# datalogger.net
KiCad netlist of a schematic drawn in EAGLE
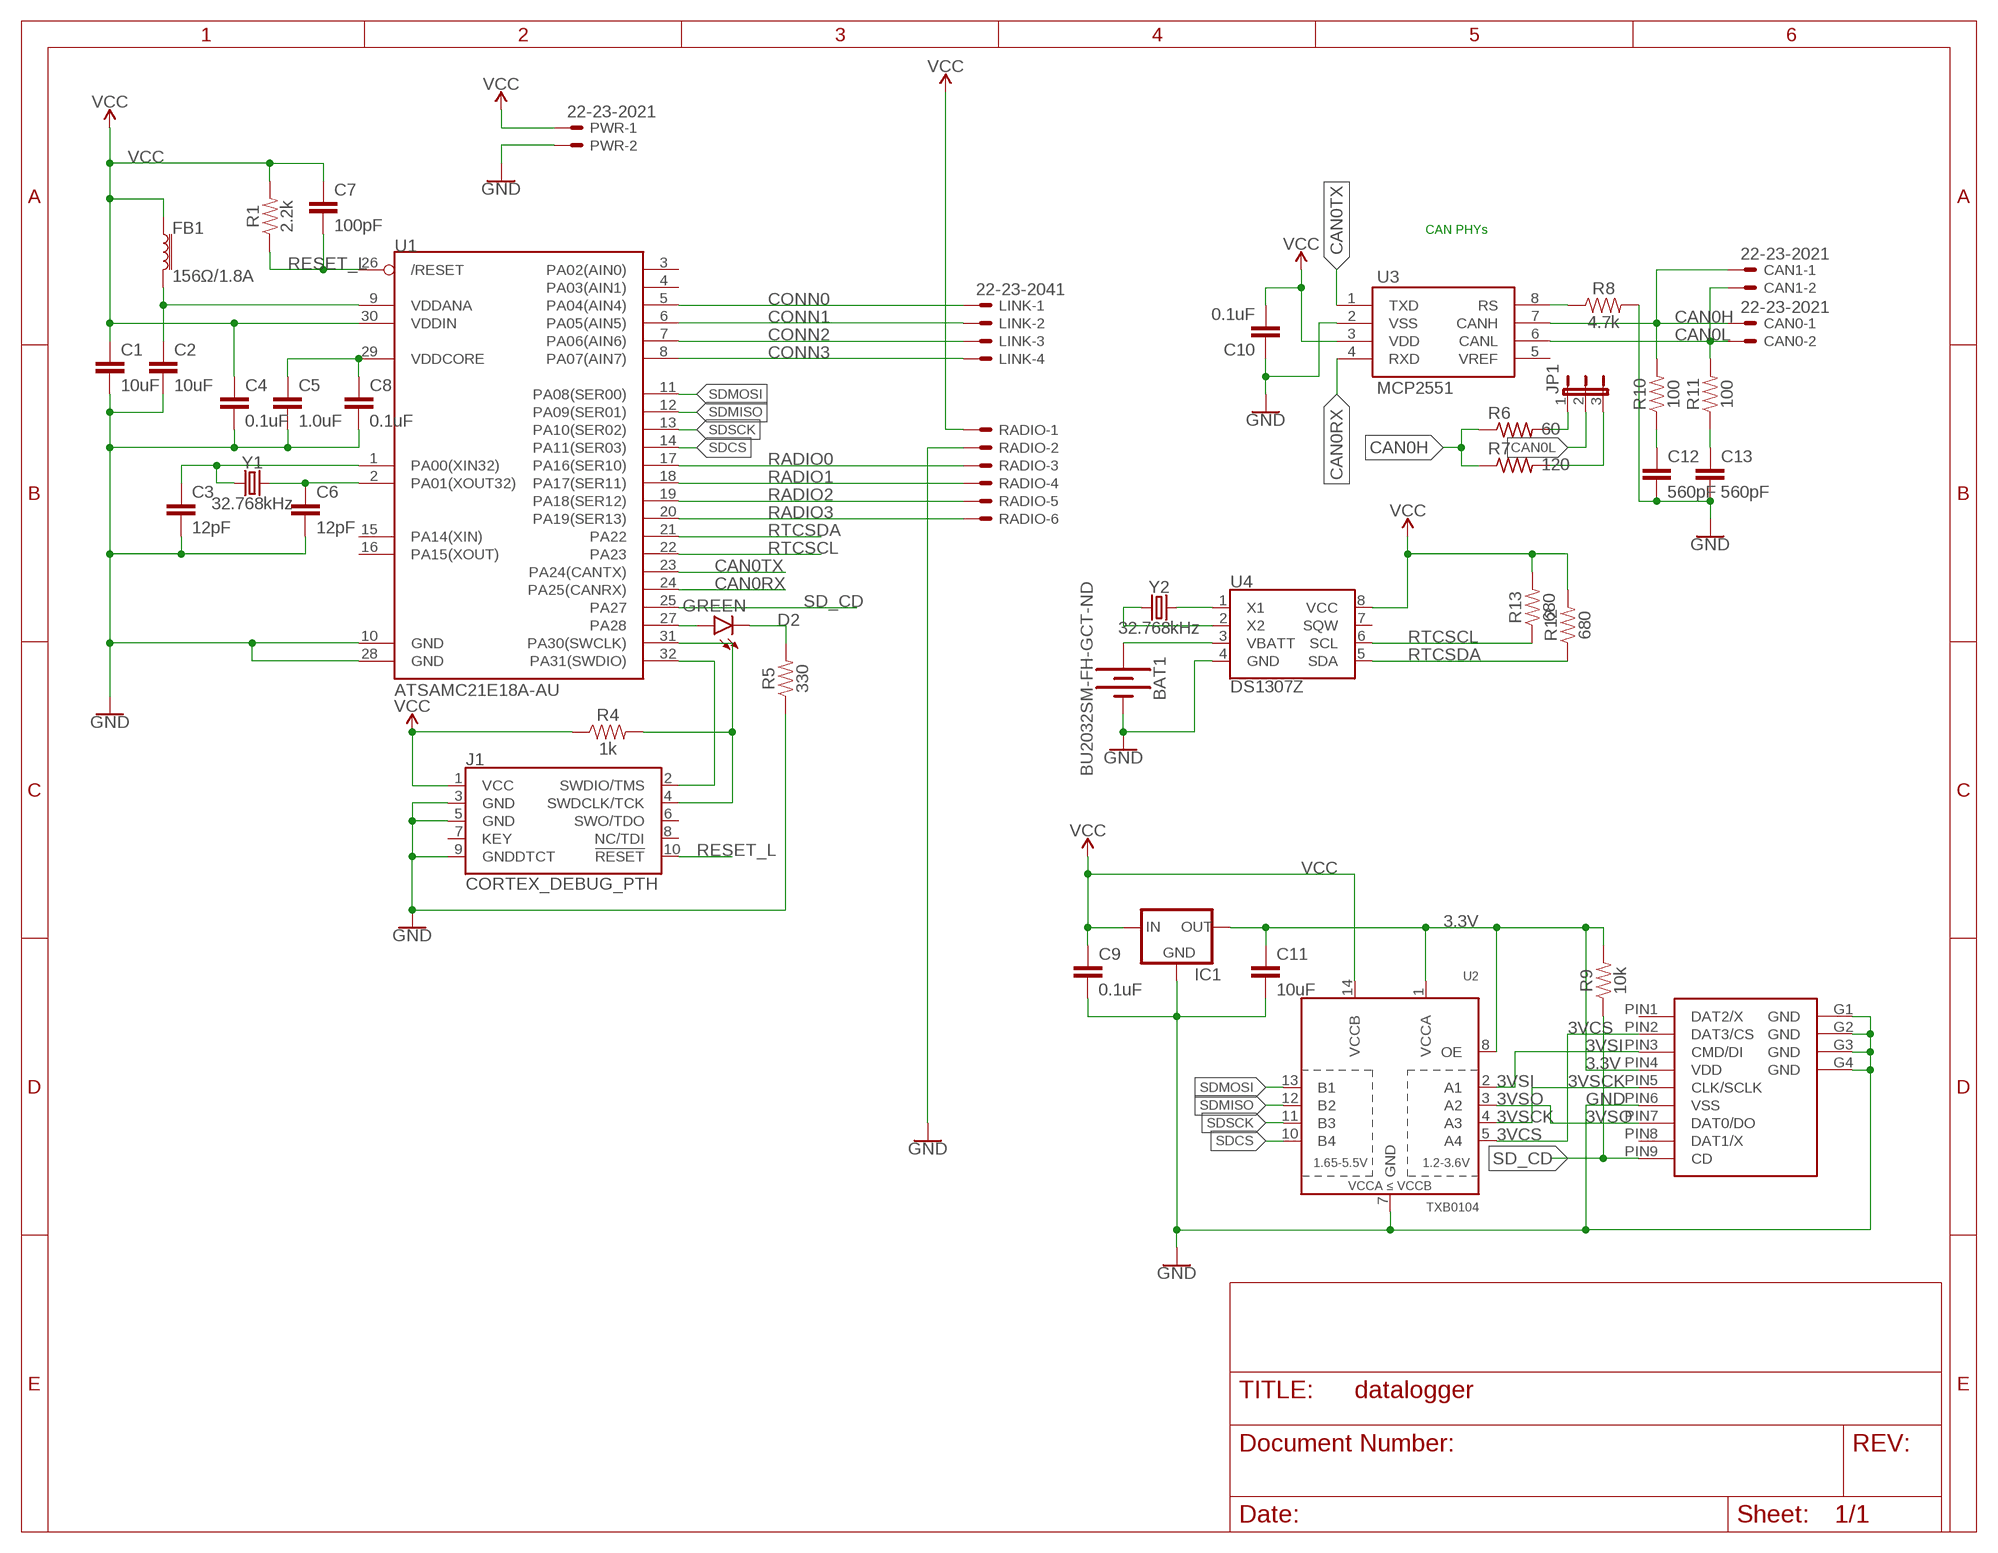
[diagram p0: schematic, sheet 1]

(export (version "E")
  (design (tool "Eeschema 10.0.6"))
  (components
    (comp (ref "BAT1")
      (value "BU2032SM-FH-GCT-ND")
      (footprint "eagle-import:BAT_BU2032SM-BT-GTR")
      (libsource (lib "eagle-import") (part "BU2032SM-FH-GCT-ND"))
    )
    (comp (ref "C1")
      (value "10uF")
      (footprint "eagle-import:0603")
      (libsource (lib "eagle-import") (part "10UF-0603-6.3V-20%"))
    )
    (comp (ref "C2")
      (value "10uF")
      (footprint "eagle-import:0603")
      (libsource (lib "eagle-import") (part "10UF-0603-6.3V-20%"))
    )
    (comp (ref "C3")
      (value "12pF")
      (footprint "eagle-import:0603")
      (libsource (lib "eagle-import") (part "12PF-0603-50V-5%"))
    )
    (comp (ref "C4")
      (value "0.1uF")
      (footprint "eagle-import:0603")
      (libsource (lib "eagle-import") (part "0.1UF-0603-25V-(+80/-20%)"))
    )
    (comp (ref "C5")
      (value "1.0uF")
      (footprint "eagle-import:0603")
      (libsource (lib "eagle-import") (part "1.0UF-0603-16V-10%"))
    )
    (comp (ref "C6")
      (value "12pF")
      (footprint "eagle-import:0603")
      (libsource (lib "eagle-import") (part "12PF-0603-50V-5%"))
    )
    (comp (ref "C7")
      (value "100pF")
      (footprint "eagle-import:0603")
      (libsource (lib "eagle-import") (part "100PF-0603-50V-5%"))
    )
    (comp (ref "C8")
      (value "0.1uF")
      (footprint "eagle-import:0603")
      (libsource (lib "eagle-import") (part "0.1UF-0603-25V-(+80/-20%)"))
    )
    (comp (ref "C9")
      (value "0.1uF")
      (footprint "eagle-import:0603")
      (libsource (lib "eagle-import") (part "0.1UF-0603-25V-(+80/-20%)"))
    )
    (comp (ref "C10")
      (value "0.1uF")
      (footprint "eagle-import:0603")
      (libsource (lib "eagle-import") (part "0.1UF-0603-25V-(+80/-20%)"))
    )
    (comp (ref "C11")
      (value "10uF")
      (footprint "eagle-import:0603")
      (libsource (lib "eagle-import") (part "10UF-0603-6.3V-20%"))
    )
    (comp (ref "C12")
      (value "560pF")
      (footprint "eagle-import:0603")
      (libsource (lib "eagle-import") (part "560PF-0603-50V-5%"))
    )
    (comp (ref "C13")
      (value "560pF")
      (footprint "eagle-import:0603")
      (libsource (lib "eagle-import") (part "560PF-0603-50V-5%"))
    )
    (comp (ref "CAN0")
      (value "22-23-2021")
      (footprint "eagle-import:22-23-2021")
      (fields (field (name "MF") "MOLEX"))
      (libsource (lib "eagle-import") (part "22-23-2021"))
    )
    (comp (ref "CAN1")
      (value "22-23-2021")
      (footprint "eagle-import:22-23-2021")
      (fields (field (name "MF") "MOLEX"))
      (libsource (lib "eagle-import") (part "22-23-2021"))
    )
    (comp (ref "D2")
      (value "GREEN")
      (footprint "eagle-import:LED_3MM")
      (libsource (lib "eagle-import") (part "LED3MM"))
    )
    (comp (ref "FB1")
      (value "156Ω/1.8A")
      (footprint "eagle-import:0603")
      (libsource (lib "eagle-import") (part "FERRITE_BEAD-0603"))
    )
    (comp (ref "IC1")
      (value "78LXX")
      (footprint "eagle-import:78LXX")
      (libsource (lib "eagle-import") (part "78LXX"))
    )
    (comp (ref "J1")
      (value "CORTEX_DEBUG_PTH")
      (footprint "eagle-import:2X5-PTH-1.27MM")
      (libsource (lib "eagle-import") (part "CORTEX_DEBUG_PTH"))
    )
    (comp (ref "JP1")
      (value "JP2E")
      (footprint "eagle-import:JP2")
      (libsource (lib "eagle-import") (part "JP2E"))
    )
    (comp (ref "LINK")
      (value "22-23-2041")
      (footprint "eagle-import:22-23-2041")
      (fields (field (name "MF") "MOLEX"))
      (libsource (lib "eagle-import") (part "22-23-2041"))
    )
    (comp (ref "PWR")
      (value "22-23-2021")
      (footprint "eagle-import:22-23-2021")
      (fields (field (name "MF") "MOLEX"))
      (libsource (lib "eagle-import") (part "22-23-2021"))
    )
    (comp (ref "R1")
      (value "2.2k")
      (footprint "eagle-import:0603")
      (libsource (lib "eagle-import") (part "2.2KOHM-0603-1/10W-1%"))
    )
    (comp (ref "R4")
      (value "1k")
      (footprint "eagle-import:0603")
      (libsource (lib "eagle-import") (part "1KOHM-0603-1/10W-1%"))
    )
    (comp (ref "R5")
      (value "330")
      (footprint "eagle-import:0603")
      (libsource (lib "eagle-import") (part "330OHM-0603-1/10W-1%"))
    )
    (comp (ref "R6")
      (value "60")
      (footprint "eagle-import:R0603")
      (libsource (lib "eagle-import") (part "R-US_R0603"))
    )
    (comp (ref "R7")
      (value "120")
      (footprint "eagle-import:R0603")
      (libsource (lib "eagle-import") (part "R-US_R0603"))
    )
    (comp (ref "R8")
      (value "4.7k")
      (footprint "eagle-import:0603")
      (libsource (lib "eagle-import") (part "4.7KOHM-0603-1/10W-1%"))
    )
    (comp (ref "R9")
      (value "10k")
      (footprint "eagle-import:0603")
      (libsource (lib "eagle-import") (part "10KOHM-0603-1/10W-1%"))
    )
    (comp (ref "R10")
      (value "100")
      (footprint "eagle-import:0603")
      (libsource (lib "eagle-import") (part "100OHM-0603-1/4W-5%"))
    )
    (comp (ref "R11")
      (value "100")
      (footprint "eagle-import:0603")
      (libsource (lib "eagle-import") (part "100OHM-0603-1/4W-5%"))
    )
    (comp (ref "R12")
      (value "680")
      (footprint "eagle-import:0603")
      (libsource (lib "eagle-import") (part "680OHM-0603-1/10W-5%"))
    )
    (comp (ref "R13")
      (value "680")
      (footprint "eagle-import:0603")
      (libsource (lib "eagle-import") (part "680OHM-0603-1/10W-5%"))
    )
    (comp (ref "RADIO")
      (value "22-23-2061")
      (footprint "eagle-import:22-23-2061")
      (fields (field (name "MF") "MOLEX"))
      (libsource (lib "eagle-import") (part "22-23-2061"))
    )
    (comp (ref "SD1")
      (value "WM14405CT-ND")
      (footprint "eagle-import:1051620001-SMD")
      (libsource (lib "eagle-import") (part "WM14405CT-ND"))
    )
    (comp (ref "U1")
      (value "ATSAMC21E18A-AU")
      (footprint "eagle-import:TQFP32-08")
      (libsource (lib "eagle-import") (part "ATSAMC21E18A-AU"))
    )
    (comp (ref "U2")
      (value "TXB0104")
      (footprint "eagle-import:TSSOP14")
      (libsource (lib "eagle-import") (part "TXB0104PWR"))
    )
    (comp (ref "U3")
      (value "MCP2551")
      (footprint "eagle-import:SO08")
      (libsource (lib "eagle-import") (part "MCP2551"))
    )
    (comp (ref "U4")
      (value "DS1307Z")
      (footprint "eagle-import:SO08-0.15")
      (libsource (lib "eagle-import") (part "DS1307Z"))
    )
    (comp (ref "Y1")
      (value "32.768kHz")
      (footprint "eagle-import:CRYSTAL-PTH-2X6-CYL")
      (libsource (lib "eagle-import") (part "CRYSTAL-32.768KHZPTH-2X6"))
    )
    (comp (ref "Y2")
      (value "32.768kHz")
      (footprint "eagle-import:CRYSTAL-PTH-2X6-CYL")
      (libsource (lib "eagle-import") (part "CRYSTAL-32.768KHZPTH-2X6"))
    )
  )
  (nets
    (net (code "1") (name "/3.3V") (class "Default")
      (node (ref "C11") (pin "1") (pinfunction "1_1") (pintype "passive"))
      (node (ref "IC1") (pin "OUT") (pinfunction "OUT_OUT") (pintype "passive"))
      (node (ref "R9") (pin "2") (pinfunction "2_2") (pintype "passive"))
      (node (ref "SD1") (pin "PIN4") (pinfunction "VDD_PIN4") (pintype "power_in"))
      (node (ref "U2") (pin "1") (pinfunction "VCCA_1") (pintype "bidirectional"))
      (node (ref "U2") (pin "8") (pinfunction "OE_8") (pintype "bidirectional"))
    )
    (net (code "2") (name "/3VCS") (class "Default")
      (node (ref "SD1") (pin "PIN2") (pinfunction "DAT3/CS_PIN2") (pintype "bidirectional"))
      (node (ref "U2") (pin "5") (pinfunction "A4_5") (pintype "bidirectional"))
    )
    (net (code "3") (name "/3VSCK") (class "Default")
      (node (ref "SD1") (pin "PIN5") (pinfunction "CLK/SCLK_PIN5") (pintype "bidirectional"))
      (node (ref "U2") (pin "4") (pinfunction "A3_4") (pintype "bidirectional"))
    )
    (net (code "4") (name "/3VSI") (class "Default")
      (node (ref "SD1") (pin "PIN3") (pinfunction "CMD/DI_PIN3") (pintype "bidirectional"))
      (node (ref "U2") (pin "2") (pinfunction "A1_2") (pintype "bidirectional"))
    )
    (net (code "5") (name "/3VSO") (class "Default")
      (node (ref "SD1") (pin "PIN7") (pinfunction "DAT0/DO_PIN7") (pintype "bidirectional"))
      (node (ref "U2") (pin "3") (pinfunction "A2_3") (pintype "bidirectional"))
    )
    (net (code "6") (name "/CONN0") (class "Default")
      (node (ref "LINK") (pin "1") (pinfunction "S_1") (pintype "passive"))
      (node (ref "U1") (pin "5") (pinfunction "PA04(AIN4)_5") (pintype "bidirectional"))
    )
    (net (code "7") (name "/CONN1") (class "Default")
      (node (ref "LINK") (pin "2") (pinfunction "S_2") (pintype "passive"))
      (node (ref "U1") (pin "6") (pinfunction "PA05(AIN5)_6") (pintype "bidirectional"))
    )
    (net (code "8") (name "/CONN2") (class "Default")
      (node (ref "LINK") (pin "3") (pinfunction "S_3") (pintype "passive"))
      (node (ref "U1") (pin "7") (pinfunction "PA06(AIN6)_7") (pintype "bidirectional"))
    )
    (net (code "9") (name "/CONN3") (class "Default")
      (node (ref "LINK") (pin "4") (pinfunction "S_4") (pintype "passive"))
      (node (ref "U1") (pin "8") (pinfunction "PA07(AIN7)_8") (pintype "bidirectional"))
    )
    (net (code "10") (name "/RADIO0") (class "Default")
      (node (ref "RADIO") (pin "3") (pinfunction "S_3") (pintype "passive"))
      (node (ref "U1") (pin "17") (pinfunction "PA16(SER10)_17") (pintype "bidirectional"))
    )
    (net (code "11") (name "/RADIO1") (class "Default")
      (node (ref "RADIO") (pin "4") (pinfunction "S_4") (pintype "passive"))
      (node (ref "U1") (pin "18") (pinfunction "PA17(SER11)_18") (pintype "bidirectional"))
    )
    (net (code "12") (name "/RADIO2") (class "Default")
      (node (ref "RADIO") (pin "5") (pinfunction "S_5") (pintype "passive"))
      (node (ref "U1") (pin "19") (pinfunction "PA18(SER12)_19") (pintype "bidirectional"))
    )
    (net (code "13") (name "/RADIO3") (class "Default")
      (node (ref "RADIO") (pin "6") (pinfunction "S_6") (pintype "passive"))
      (node (ref "U1") (pin "20") (pinfunction "PA19(SER13)_20") (pintype "bidirectional"))
    )
    (net (code "14") (name "/RESET_L") (class "Default")
      (node (ref "C7") (pin "2") (pinfunction "2_2") (pintype "passive"))
      (node (ref "J1") (pin "10") (pinfunction "~{RESET}_10") (pintype "bidirectional"))
      (node (ref "R1") (pin "1") (pinfunction "1_1") (pintype "passive"))
      (node (ref "U1") (pin "26") (pinfunction "/RESET_26") (pintype "input"))
    )
    (net (code "15") (name "/RTCSCL") (class "Default")
      (node (ref "R13") (pin "1") (pinfunction "1_1") (pintype "passive"))
      (node (ref "U1") (pin "22") (pinfunction "PA23_22") (pintype "bidirectional"))
      (node (ref "U4") (pin "6") (pinfunction "SCL_6") (pintype "bidirectional"))
    )
    (net (code "16") (name "/RTCSDA") (class "Default")
      (node (ref "R12") (pin "1") (pinfunction "1_1") (pintype "passive"))
      (node (ref "U1") (pin "21") (pinfunction "PA22_21") (pintype "bidirectional"))
      (node (ref "U4") (pin "5") (pinfunction "SDA_5") (pintype "bidirectional"))
    )
    (net (code "17") (name "CAN0H") (class "Default")
      (node (ref "CAN0") (pin "1") (pinfunction "S_1") (pintype "passive"))
      (node (ref "CAN1") (pin "1") (pinfunction "S_1") (pintype "passive"))
      (node (ref "R10") (pin "2") (pinfunction "2_2") (pintype "passive"))
      (node (ref "R6") (pin "1") (pinfunction "1_1") (pintype "passive"))
      (node (ref "R7") (pin "1") (pinfunction "1_1") (pintype "passive"))
      (node (ref "U3") (pin "7") (pinfunction "CANH_7") (pintype "bidirectional"))
    )
    (net (code "18") (name "CAN0L") (class "Default")
      (node (ref "CAN0") (pin "2") (pinfunction "S_2") (pintype "passive"))
      (node (ref "CAN1") (pin "2") (pinfunction "S_2") (pintype "passive"))
      (node (ref "JP1") (pin "2") (pinfunction "2_2") (pintype "passive"))
      (node (ref "R11") (pin "2") (pinfunction "2_2") (pintype "passive"))
      (node (ref "U3") (pin "6") (pinfunction "CANL_6") (pintype "bidirectional"))
    )
    (net (code "19") (name "CAN0RX") (class "Default")
      (node (ref "U1") (pin "24") (pinfunction "PA25(CANRX)_24") (pintype "bidirectional"))
      (node (ref "U3") (pin "4") (pinfunction "RXD_4") (pintype "bidirectional"))
    )
    (net (code "20") (name "CAN0TX") (class "Default")
      (node (ref "U1") (pin "23") (pinfunction "PA24(CANTX)_23") (pintype "bidirectional"))
      (node (ref "U3") (pin "1") (pinfunction "TXD_1") (pintype "bidirectional"))
    )
    (net (code "21") (name "GND") (class "Default")
      (node (ref "BAT1") (pin "2") (pinfunction "-_2") (pintype "power_in"))
      (node (ref "C1") (pin "2") (pinfunction "2_2") (pintype "passive"))
      (node (ref "C10") (pin "1") (pinfunction "1_1") (pintype "passive"))
      (node (ref "C11") (pin "2") (pinfunction "2_2") (pintype "passive"))
      (node (ref "C12") (pin "2") (pinfunction "2_2") (pintype "passive"))
      (node (ref "C13") (pin "2") (pinfunction "2_2") (pintype "passive"))
      (node (ref "C2") (pin "2") (pinfunction "2_2") (pintype "passive"))
      (node (ref "C3") (pin "2") (pinfunction "2_2") (pintype "passive"))
      (node (ref "C4") (pin "2") (pinfunction "2_2") (pintype "passive"))
      (node (ref "C5") (pin "2") (pinfunction "2_2") (pintype "passive"))
      (node (ref "C6") (pin "2") (pinfunction "2_2") (pintype "passive"))
      (node (ref "C8") (pin "2") (pinfunction "2_2") (pintype "passive"))
      (node (ref "C9") (pin "2") (pinfunction "2_2") (pintype "passive"))
      (node (ref "IC1") (pin "GND") (pinfunction "GND_GND") (pintype "input"))
      (node (ref "J1") (pin "3") (pinfunction "GND_3") (pintype "bidirectional"))
      (node (ref "J1") (pin "5") (pinfunction "GND_5") (pintype "bidirectional"))
      (node (ref "J1") (pin "9") (pinfunction "GNDDTCT_9") (pintype "bidirectional"))
      (node (ref "PWR") (pin "2") (pinfunction "S_2") (pintype "passive"))
      (node (ref "R5") (pin "1") (pinfunction "1_1") (pintype "passive"))
      (node (ref "R8") (pin "2") (pinfunction "2_2") (pintype "passive"))
      (node (ref "RADIO") (pin "2") (pinfunction "S_2") (pintype "passive"))
      (node (ref "SD1") (pin "G1") (pinfunction "GND_G1") (pintype "power_in"))
      (node (ref "SD1") (pin "G2") (pinfunction "GND_G2") (pintype "power_in"))
      (node (ref "SD1") (pin "G3") (pinfunction "GND_G3") (pintype "power_in"))
      (node (ref "SD1") (pin "G4") (pinfunction "GND_G4") (pintype "power_in"))
      (node (ref "SD1") (pin "PIN6") (pinfunction "VSS_PIN6") (pintype "power_in"))
      (node (ref "U1") (pin "10") (pinfunction "GND_10") (pintype "power_in"))
      (node (ref "U1") (pin "28") (pinfunction "GND_28") (pintype "power_in"))
      (node (ref "U2") (pin "7") (pinfunction "GND_7") (pintype "bidirectional"))
      (node (ref "U3") (pin "2") (pinfunction "VSS_2") (pintype "bidirectional"))
      (node (ref "U4") (pin "4") (pinfunction "GND_4") (pintype "bidirectional"))
    )
    (net (code "22") (name "Net-(BAT1-+)") (class "Default")
      (node (ref "BAT1") (pin "1") (pinfunction "+_1") (pintype "power_in"))
      (node (ref "U4") (pin "3") (pinfunction "VBATT_3") (pintype "bidirectional"))
    )
    (net (code "23") (name "Net-(C12-Pad1)") (class "Default")
      (node (ref "C12") (pin "1") (pinfunction "1_1") (pintype "passive"))
      (node (ref "R10") (pin "1") (pinfunction "1_1") (pintype "passive"))
    )
    (net (code "24") (name "Net-(C13-Pad1)") (class "Default")
      (node (ref "C13") (pin "1") (pinfunction "1_1") (pintype "passive"))
      (node (ref "R11") (pin "1") (pinfunction "1_1") (pintype "passive"))
    )
    (net (code "25") (name "Net-(D2-C)") (class "Default")
      (node (ref "D2") (pin "K") (pinfunction "C_K") (pintype "passive"))
      (node (ref "R5") (pin "2") (pinfunction "2_2") (pintype "passive"))
    )
    (net (code "26") (name "Net-(J1-SWDCLK{slash}TCK)") (class "Default")
      (node (ref "J1") (pin "4") (pinfunction "SWDCLK/TCK_4") (pintype "bidirectional"))
      (node (ref "R4") (pin "2") (pinfunction "2_2") (pintype "passive"))
      (node (ref "U1") (pin "31") (pinfunction "PA30(SWCLK)_31") (pintype "bidirectional"))
    )
    (net (code "27") (name "Net-(J1-SWDIO{slash}TMS)") (class "Default")
      (node (ref "J1") (pin "2") (pinfunction "SWDIO/TMS_2") (pintype "bidirectional"))
      (node (ref "U1") (pin "32") (pinfunction "PA31(SWDIO)_32") (pintype "bidirectional"))
    )
    (net (code "28") (name "Net-(JP1-Pad1)") (class "Default")
      (node (ref "JP1") (pin "1") (pinfunction "1_1") (pintype "passive"))
      (node (ref "R6") (pin "2") (pinfunction "2_2") (pintype "passive"))
    )
    (net (code "29") (name "Net-(JP1-Pad3)") (class "Default")
      (node (ref "JP1") (pin "3") (pinfunction "3_3") (pintype "passive"))
      (node (ref "R7") (pin "2") (pinfunction "2_2") (pintype "passive"))
    )
    (net (code "30") (name "Net-(U1-PA00(XIN32))") (class "Default")
      (node (ref "C3") (pin "1") (pinfunction "1_1") (pintype "passive"))
      (node (ref "U1") (pin "1") (pinfunction "PA00(XIN32)_1") (pintype "bidirectional"))
      (node (ref "Y1") (pin "1") (pinfunction "1_1") (pintype "passive"))
    )
    (net (code "31") (name "Net-(U1-PA01(XOUT32))") (class "Default")
      (node (ref "C6") (pin "1") (pinfunction "1_1") (pintype "passive"))
      (node (ref "U1") (pin "2") (pinfunction "PA01(XOUT32)_2") (pintype "bidirectional"))
      (node (ref "Y1") (pin "2") (pinfunction "2_2") (pintype "passive"))
    )
    (net (code "32") (name "Net-(U1-PA28)") (class "Default")
      (node (ref "D2") (pin "A") (pinfunction "A_A") (pintype "passive"))
      (node (ref "U1") (pin "27") (pinfunction "PA28_27") (pintype "bidirectional"))
    )
    (net (code "33") (name "Net-(U1-VDDANA)") (class "Default")
      (node (ref "C2") (pin "1") (pinfunction "1_1") (pintype "passive"))
      (node (ref "FB1") (pin "2") (pinfunction "2_2") (pintype "passive"))
      (node (ref "U1") (pin "9") (pinfunction "VDDANA_9") (pintype "power_in"))
    )
    (net (code "34") (name "Net-(U1-VDDCORE)") (class "Default")
      (node (ref "C5") (pin "1") (pinfunction "1_1") (pintype "passive"))
      (node (ref "C8") (pin "1") (pinfunction "1_1") (pintype "passive"))
      (node (ref "U1") (pin "29") (pinfunction "VDDCORE_29") (pintype "output"))
    )
    (net (code "35") (name "Net-(U3-RS)") (class "Default")
      (node (ref "R8") (pin "1") (pinfunction "1_1") (pintype "passive"))
      (node (ref "U3") (pin "8") (pinfunction "RS_8") (pintype "bidirectional"))
    )
    (net (code "36") (name "Net-(U4-X1)") (class "Default")
      (node (ref "U4") (pin "1") (pinfunction "X1_1") (pintype "bidirectional"))
      (node (ref "Y2") (pin "2") (pinfunction "2_2") (pintype "passive"))
    )
    (net (code "37") (name "Net-(U4-X2)") (class "Default")
      (node (ref "U4") (pin "2") (pinfunction "X2_2") (pintype "bidirectional"))
      (node (ref "Y2") (pin "1") (pinfunction "1_1") (pintype "passive"))
    )
    (net (code "38") (name "SDCS") (class "Default")
      (node (ref "U1") (pin "14") (pinfunction "PA11(SER03)_14") (pintype "bidirectional"))
      (node (ref "U2") (pin "10") (pinfunction "B4_10") (pintype "bidirectional"))
    )
    (net (code "39") (name "SDMISO") (class "Default")
      (node (ref "U1") (pin "12") (pinfunction "PA09(SER01)_12") (pintype "bidirectional"))
      (node (ref "U2") (pin "12") (pinfunction "B2_12") (pintype "bidirectional"))
    )
    (net (code "40") (name "SDMOSI") (class "Default")
      (node (ref "U1") (pin "11") (pinfunction "PA08(SER00)_11") (pintype "bidirectional"))
      (node (ref "U2") (pin "13") (pinfunction "B1_13") (pintype "bidirectional"))
    )
    (net (code "41") (name "SDSCK") (class "Default")
      (node (ref "U1") (pin "13") (pinfunction "PA10(SER02)_13") (pintype "bidirectional"))
      (node (ref "U2") (pin "11") (pinfunction "B3_11") (pintype "bidirectional"))
    )
    (net (code "42") (name "SD_CD") (class "Default")
      (node (ref "R9") (pin "1") (pinfunction "1_1") (pintype "passive"))
      (node (ref "SD1") (pin "PIN9") (pinfunction "CD_PIN9") (pintype "bidirectional"))
      (node (ref "U1") (pin "25") (pinfunction "PA27_25") (pintype "bidirectional"))
    )
    (net (code "43") (name "VCC") (class "Default")
      (node (ref "C1") (pin "1") (pinfunction "1_1") (pintype "passive"))
      (node (ref "C10") (pin "2") (pinfunction "2_2") (pintype "passive"))
      (node (ref "C4") (pin "1") (pinfunction "1_1") (pintype "passive"))
      (node (ref "C7") (pin "1") (pinfunction "1_1") (pintype "passive"))
      (node (ref "C9") (pin "1") (pinfunction "1_1") (pintype "passive"))
      (node (ref "FB1") (pin "1") (pinfunction "1_1") (pintype "passive"))
      (node (ref "IC1") (pin "IN") (pinfunction "IN_IN") (pintype "input"))
      (node (ref "J1") (pin "1") (pinfunction "VCC_1") (pintype "bidirectional"))
      (node (ref "PWR") (pin "1") (pinfunction "S_1") (pintype "passive"))
      (node (ref "R1") (pin "2") (pinfunction "2_2") (pintype "passive"))
      (node (ref "R12") (pin "2") (pinfunction "2_2") (pintype "passive"))
      (node (ref "R13") (pin "2") (pinfunction "2_2") (pintype "passive"))
      (node (ref "R4") (pin "1") (pinfunction "1_1") (pintype "passive"))
      (node (ref "RADIO") (pin "1") (pinfunction "S_1") (pintype "passive"))
      (node (ref "U1") (pin "30") (pinfunction "VDDIN_30") (pintype "power_in"))
      (node (ref "U2") (pin "14") (pinfunction "VCCB_14") (pintype "bidirectional"))
      (node (ref "U3") (pin "3") (pinfunction "VDD_3") (pintype "bidirectional"))
      (node (ref "U4") (pin "8") (pinfunction "VCC_8") (pintype "bidirectional"))
    )
    (net (code "44") (name "unconnected-(J1-KEY-Pad7)") (class "Default")
      (node (ref "J1") (pin "7") (pinfunction "KEY_7") (pintype "bidirectional"))
    )
    (net (code "45") (name "unconnected-(J1-NC{slash}TDI-Pad8)") (class "Default")
      (node (ref "J1") (pin "8") (pinfunction "NC/TDI_8") (pintype "bidirectional"))
    )
    (net (code "46") (name "unconnected-(J1-SWO{slash}TDO-Pad6)") (class "Default")
      (node (ref "J1") (pin "6") (pinfunction "SWO/TDO_6") (pintype "bidirectional"))
    )
    (net (code "47") (name "unconnected-(SD1-DAT1{slash}X-PadPIN8)") (class "Default")
      (node (ref "SD1") (pin "PIN8") (pinfunction "DAT1/X_PIN8") (pintype "bidirectional"))
    )
    (net (code "48") (name "unconnected-(SD1-DAT2{slash}X-PadPIN1)") (class "Default")
      (node (ref "SD1") (pin "PIN1") (pinfunction "DAT2/X_PIN1") (pintype "bidirectional"))
    )
    (net (code "49") (name "unconnected-(U1-PA02(AIN0)-Pad3)") (class "Default")
      (node (ref "U1") (pin "3") (pinfunction "PA02(AIN0)_3") (pintype "bidirectional"))
    )
    (net (code "50") (name "unconnected-(U1-PA03(AIN1)-Pad4)") (class "Default")
      (node (ref "U1") (pin "4") (pinfunction "PA03(AIN1)_4") (pintype "bidirectional"))
    )
    (net (code "51") (name "unconnected-(U1-PA14(XIN)-Pad15)") (class "Default")
      (node (ref "U1") (pin "15") (pinfunction "PA14(XIN)_15") (pintype "bidirectional"))
    )
    (net (code "52") (name "unconnected-(U1-PA15(XOUT)-Pad16)") (class "Default")
      (node (ref "U1") (pin "16") (pinfunction "PA15(XOUT)_16") (pintype "bidirectional"))
    )
    (net (code "53") (name "unconnected-(U3-VREF-Pad5)") (class "Default")
      (node (ref "U3") (pin "5") (pinfunction "VREF_5") (pintype "bidirectional"))
    )
    (net (code "54") (name "unconnected-(U4-SQW-Pad7)") (class "Default")
      (node (ref "U4") (pin "7") (pinfunction "SQW_7") (pintype "bidirectional"))
    )
  )
)
